# wire_cutter_sch.net
KiCad netlist of a schematic drawn in Altium Designer
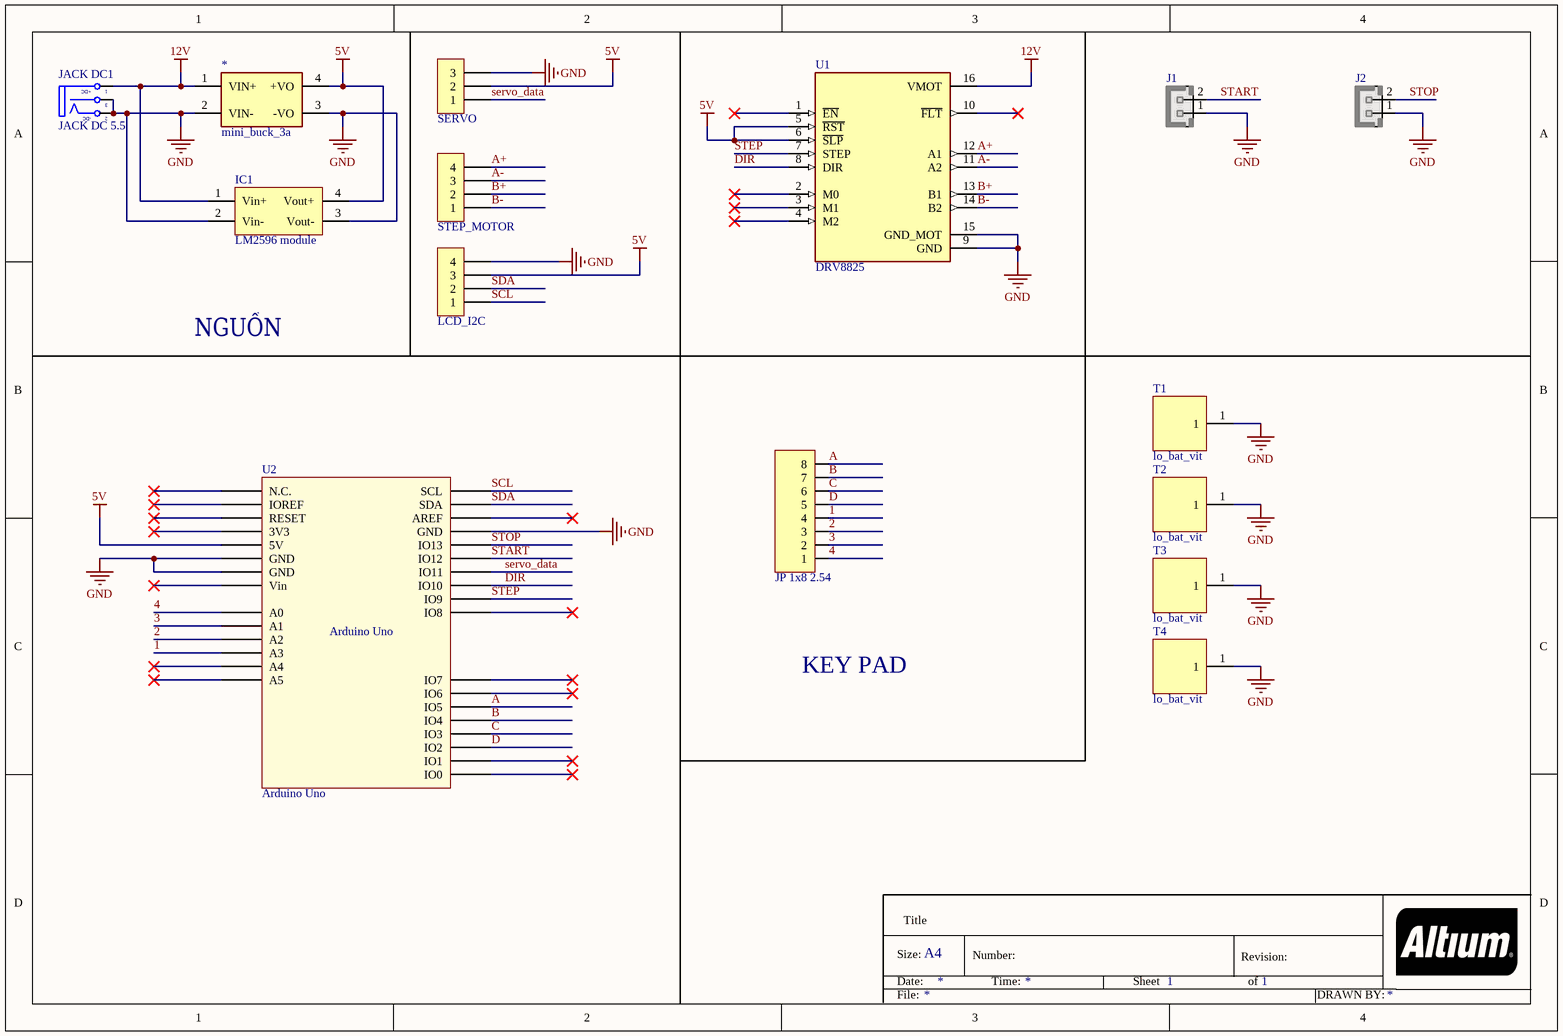
[diagram p0: wire_cutter_sch.SchDoc]

(export (version "E")
  (design (tool "Eeschema 10.0.6"))
  (components
    (comp (ref "*")
      (value "mini_buck_3a")
      (footprint "MINI_BUCK_3A")
      (libsource (lib "Thu_Vien_nguyen_Viet_Hoang") (part "mini_buck_3a"))
    )
    (comp (ref "H1")
      (value "SERVO")
      (footprint "Header 3P DC 2.54")
      (description "Cắm")
      (libsource (lib "Thu_Vien_nguyen_Viet_Hoang") (part "Header 3P 2.54 Duc Cong"))
    )
    (comp (ref "H2")
      (value "STEP_MOTOR")
      (footprint "Header 4P DC 2.54")
      (description "Cắm")
      (libsource (lib "Thu_Vien_nguyen_Viet_Hoang") (part "Header 4P 2.54 Duc Cong"))
    )
    (comp (ref "H3")
      (value "LCD_I2C")
      (footprint "Header 4P DC 2.54")
      (description "Cắm")
      (libsource (lib "Thu_Vien_nguyen_Viet_Hoang") (part "Header 4P 2.54 Duc Cong"))
    )
    (comp (ref "IC1")
      (value "LM2596 module")
      (footprint "LM2596 Module")
      (libsource (lib "Thu_Vien_nguyen_Viet_Hoang") (part "LM2596 module"))
    )
    (comp (ref "J1")
      (value "HHDR_2")
      (footprint "XH_2")
      (description "JST-XH pitch: 2.5mm")
      (libsource (lib "Thu_Vien_nguyen_Viet_Hoang") (part "XH_2"))
    )
    (comp (ref "J2")
      (value "HHDR_2")
      (footprint "XH_2")
      (description "JST-XH pitch: 2.5mm")
      (libsource (lib "Thu_Vien_nguyen_Viet_Hoang") (part "XH_2"))
    )
    (comp (ref "JACK DC1")
      (value "JACK DC 5.5")
      (footprint "JACK DC 5.5")
      (libsource (lib "Thu_Vien_nguyen_Viet_Hoang") (part "JACK DC 5.5"))
    )
    (comp (ref "JP1")
      (value "JP 1x8 2.54")
      (footprint "JP 1x8 DT")
      (description "Cắm")
      (libsource (lib "Thu_Vien_nguyen_Viet_Hoang") (part "JP 1x8 2.54 Duc Thang"))
    )
    (comp (ref "T1")
      (value "lo_bat_vit")
      (footprint "lo_bat_vit")
      (libsource (lib "Thu_Vien_nguyen_Viet_Hoang") (part "lo_bat_vit"))
    )
    (comp (ref "T2")
      (value "lo_bat_vit")
      (footprint "lo_bat_vit")
      (libsource (lib "Thu_Vien_nguyen_Viet_Hoang") (part "lo_bat_vit"))
    )
    (comp (ref "T3")
      (value "lo_bat_vit")
      (footprint "lo_bat_vit")
      (libsource (lib "Thu_Vien_nguyen_Viet_Hoang") (part "lo_bat_vit"))
    )
    (comp (ref "T4")
      (value "lo_bat_vit")
      (footprint "lo_bat_vit")
      (libsource (lib "Thu_Vien_nguyen_Viet_Hoang") (part "lo_bat_vit"))
    )
    (comp (ref "U1")
      (value "DRV8825")
      (footprint "DRV8825")
      (libsource (lib "Thu_Vien_nguyen_Viet_Hoang") (part "DRV8825"))
    )
    (comp (ref "U2")
      (value "Arduino Uno")
      (footprint "Arduino Uno")
      (libsource (lib "Thu_Vien_nguyen_Viet_Hoang") (part "Arduino Uno"))
    )
  )
  (nets
    (net (code "1") (name "/1") (class "Default")
      (node (ref "JP1") (pin "4") (pinfunction "4_4") (pintype "passive"))
      (node (ref "U2") (pin "A3") (pinfunction "A3_A3") (pintype "passive"))
    )
    (net (code "2") (name "/2") (class "Default")
      (node (ref "JP1") (pin "3") (pinfunction "3_3") (pintype "passive"))
      (node (ref "U2") (pin "A2") (pinfunction "A2_A2") (pintype "passive"))
    )
    (net (code "3") (name "/3") (class "Default")
      (node (ref "JP1") (pin "2") (pinfunction "2_2") (pintype "passive"))
      (node (ref "U2") (pin "A1") (pinfunction "A1_A1") (pintype "passive"))
    )
    (net (code "4") (name "/4") (class "Default")
      (node (ref "JP1") (pin "1") (pinfunction "1_1") (pintype "passive"))
      (node (ref "U2") (pin "A0") (pinfunction "A0_A0") (pintype "passive"))
    )
    (net (code "5") (name "/A") (class "Default")
      (node (ref "JP1") (pin "8") (pinfunction "8_8") (pintype "passive"))
      (node (ref "U2") (pin "5") (pinfunction "IO5_5") (pintype "passive"))
    )
    (net (code "6") (name "/A+") (class "Default")
      (node (ref "H2") (pin "4") (pinfunction "4_4") (pintype "passive"))
      (node (ref "U1") (pin "12") (pinfunction "A1_12") (pintype "output"))
    )
    (net (code "7") (name "/A-") (class "Default")
      (node (ref "H2") (pin "3") (pinfunction "3_3") (pintype "passive"))
      (node (ref "U1") (pin "11") (pinfunction "A2_11") (pintype "output"))
    )
    (net (code "8") (name "/B") (class "Default")
      (node (ref "JP1") (pin "7") (pinfunction "7_7") (pintype "passive"))
      (node (ref "U2") (pin "4") (pinfunction "IO4_4") (pintype "passive"))
    )
    (net (code "9") (name "/B+") (class "Default")
      (node (ref "H2") (pin "2") (pinfunction "2_2") (pintype "passive"))
      (node (ref "U1") (pin "13") (pinfunction "B1_13") (pintype "output"))
    )
    (net (code "10") (name "/B-") (class "Default")
      (node (ref "H2") (pin "1") (pinfunction "1_1") (pintype "passive"))
      (node (ref "U1") (pin "14") (pinfunction "B2_14") (pintype "output"))
    )
    (net (code "11") (name "/C") (class "Default")
      (node (ref "JP1") (pin "6") (pinfunction "6_6") (pintype "passive"))
      (node (ref "U2") (pin "3") (pinfunction "IO3_3") (pintype "passive"))
    )
    (net (code "12") (name "/D") (class "Default")
      (node (ref "JP1") (pin "5") (pinfunction "5_5") (pintype "passive"))
      (node (ref "U2") (pin "2") (pinfunction "IO2_2") (pintype "passive"))
    )
    (net (code "13") (name "/DIR") (class "Default")
      (node (ref "U1") (pin "8") (pinfunction "DIR_8") (pintype "input"))
      (node (ref "U2") (pin "10") (pinfunction "IO10_10") (pintype "passive"))
    )
    (net (code "14") (name "/SCL") (class "Default")
      (node (ref "H3") (pin "1") (pinfunction "1_1") (pintype "passive"))
      (node (ref "U2") (pin "SCL") (pinfunction "SCL_SCL") (pintype "passive"))
    )
    (net (code "15") (name "/SDA") (class "Default")
      (node (ref "H3") (pin "2") (pinfunction "2_2") (pintype "passive"))
      (node (ref "U2") (pin "SDA") (pinfunction "SDA_SDA") (pintype "passive"))
    )
    (net (code "16") (name "/START") (class "Default")
      (node (ref "J1") (pin "2") (pinfunction "2_2") (pintype "passive"))
      (node (ref "U2") (pin "12") (pinfunction "IO12_12") (pintype "passive"))
    )
    (net (code "17") (name "/STEP") (class "Default")
      (node (ref "U1") (pin "7") (pinfunction "STEP_7") (pintype "input"))
      (node (ref "U2") (pin "9") (pinfunction "IO9_9") (pintype "passive"))
    )
    (net (code "18") (name "/STOP") (class "Default")
      (node (ref "J2") (pin "2") (pinfunction "2_2") (pintype "passive"))
      (node (ref "U2") (pin "13") (pinfunction "IO13_13") (pintype "passive"))
    )
    (net (code "19") (name "/servo_data") (class "Default")
      (node (ref "H1") (pin "1") (pinfunction "1_1") (pintype "passive"))
      (node (ref "U2") (pin "11") (pinfunction "IO11_11") (pintype "passive"))
    )
    (net (code "20") (name "5V") (class "Default")
      (node (ref "*") (pin "4") (pinfunction "+VO_4") (pintype "passive"))
      (node (ref "H1") (pin "2") (pinfunction "2_2") (pintype "passive"))
      (node (ref "H3") (pin "3") (pinfunction "3_3") (pintype "passive"))
      (node (ref "IC1") (pin "4") (pinfunction "Vout+_4") (pintype "power_in"))
      (node (ref "U1") (pin "5") (pinfunction "~{RST}_5") (pintype "input"))
      (node (ref "U1") (pin "6") (pinfunction "~{SLP}_6") (pintype "input"))
      (node (ref "U2") (pin "5V") (pinfunction "5V_5V") (pintype "passive"))
    )
    (net (code "21") (name "12V") (class "Default")
      (node (ref "*") (pin "1") (pinfunction "VIN+_1") (pintype "passive"))
      (node (ref "IC1") (pin "1") (pinfunction "Vin+_1") (pintype "power_in"))
      (node (ref "JACK DC1") (pin "1") (pinfunction "T_1") (pintype "passive"))
      (node (ref "U1") (pin "16") (pinfunction "VMOT_16") (pintype "power_in"))
    )
    (net (code "22") (name "GND") (class "Default")
      (node (ref "*") (pin "2") (pinfunction "VIN-_2") (pintype "passive"))
      (node (ref "*") (pin "3") (pinfunction "-VO_3") (pintype "passive"))
      (node (ref "H1") (pin "3") (pinfunction "3_3") (pintype "passive"))
      (node (ref "H3") (pin "4") (pinfunction "4_4") (pintype "passive"))
      (node (ref "IC1") (pin "2") (pinfunction "Vin-_2") (pintype "power_in"))
      (node (ref "IC1") (pin "3") (pinfunction "Vout-_3") (pintype "power_in"))
      (node (ref "J1") (pin "1") (pinfunction "1_1") (pintype "passive"))
      (node (ref "J2") (pin "1") (pinfunction "1_1") (pintype "passive"))
      (node (ref "JACK DC1") (pin "2") (pinfunction "TN_2") (pintype "passive"))
      (node (ref "JACK DC1") (pin "3") (pinfunction "S_3") (pintype "power_in"))
      (node (ref "T1") (pin "1") (pinfunction "1_1") (pintype "passive"))
      (node (ref "T2") (pin "1") (pinfunction "1_1") (pintype "passive"))
      (node (ref "T3") (pin "1") (pinfunction "1_1") (pintype "passive"))
      (node (ref "T4") (pin "1") (pinfunction "1_1") (pintype "passive"))
      (node (ref "U1") (pin "15") (pinfunction "GND_MOT_15") (pintype "power_in"))
      (node (ref "U1") (pin "9") (pinfunction "GND_9") (pintype "power_in"))
      (node (ref "U2") (pin "GND1") (pinfunction "GND_GND1") (pintype "passive"))
      (node (ref "U2") (pin "GND2") (pinfunction "GND_GND2") (pintype "passive"))
      (node (ref "U2") (pin "GND3") (pinfunction "GND_GND3") (pintype "passive"))
    )
    (net (code "23") (name "unconnected-(U1-M0-Pad2)") (class "Default")
      (node (ref "U1") (pin "2") (pinfunction "M0_2") (pintype "input+no_connect"))
    )
    (net (code "24") (name "unconnected-(U1-M1-Pad3)") (class "Default")
      (node (ref "U1") (pin "3") (pinfunction "M1_3") (pintype "input+no_connect"))
    )
    (net (code "25") (name "unconnected-(U1-M2-Pad4)") (class "Default")
      (node (ref "U1") (pin "4") (pinfunction "M2_4") (pintype "input+no_connect"))
    )
    (net (code "26") (name "unconnected-(U1-~{EN}-Pad1)") (class "Default")
      (node (ref "U1") (pin "1") (pinfunction "~{EN}_1") (pintype "input+no_connect"))
    )
    (net (code "27") (name "unconnected-(U1-~{FLT}-Pad10)") (class "Default")
      (node (ref "U1") (pin "10") (pinfunction "~{FLT}_10") (pintype "output+no_connect"))
    )
    (net (code "28") (name "unconnected-(U2-IO0-Pad0)") (class "Default")
      (node (ref "U2") (pin "0") (pinfunction "IO0_0") (pintype "passive+no_connect"))
    )
    (net (code "29") (name "unconnected-(U2-IO1-Pad1)") (class "Default")
      (node (ref "U2") (pin "1") (pinfunction "IO1_1") (pintype "passive+no_connect"))
    )
    (net (code "30") (name "unconnected-(U2-IO6-Pad6)") (class "Default")
      (node (ref "U2") (pin "6") (pinfunction "IO6_6") (pintype "passive+no_connect"))
    )
    (net (code "31") (name "unconnected-(U2-IO7-Pad7)") (class "Default")
      (node (ref "U2") (pin "7") (pinfunction "IO7_7") (pintype "passive+no_connect"))
    )
    (net (code "32") (name "unconnected-(U2-IO8-Pad8)") (class "Default")
      (node (ref "U2") (pin "8") (pinfunction "IO8_8") (pintype "passive+no_connect"))
    )
    (net (code "33") (name "unconnected-(U2-N.C.-PadNC)") (class "Default")
      (node (ref "U2") (pin "NC") (pinfunction "N.C._NC") (pintype "passive+no_connect"))
    )
    (net (code "34") (name "unconnected-(U2-Pad3V3)") (class "Default")
      (node (ref "U2") (pin "3V3") (pinfunction "3V3_3V3") (pintype "passive+no_connect"))
    )
    (net (code "35") (name "unconnected-(U2-PadA4)") (class "Default")
      (node (ref "U2") (pin "A4") (pinfunction "A4_A4") (pintype "passive+no_connect"))
    )
    (net (code "36") (name "unconnected-(U2-PadA5)") (class "Default")
      (node (ref "U2") (pin "A5") (pinfunction "A5_A5") (pintype "passive+no_connect"))
    )
    (net (code "37") (name "unconnected-(U2-PadAREF)") (class "Default")
      (node (ref "U2") (pin "AREF") (pinfunction "AREF_AREF") (pintype "passive+no_connect"))
    )
    (net (code "38") (name "unconnected-(U2-PadIOREF)") (class "Default")
      (node (ref "U2") (pin "IOREF") (pinfunction "IOREF_IOREF") (pintype "passive+no_connect"))
    )
    (net (code "39") (name "unconnected-(U2-PadRESET)") (class "Default")
      (node (ref "U2") (pin "RESET") (pinfunction "RESET_RESET") (pintype "passive+no_connect"))
    )
    (net (code "40") (name "unconnected-(U2-PadVin)") (class "Default")
      (node (ref "U2") (pin "Vin") (pinfunction "Vin_Vin") (pintype "passive+no_connect"))
    )
  )
)
